# AccelBreakout.net
KiCad netlist of a schematic drawn in EAGLE
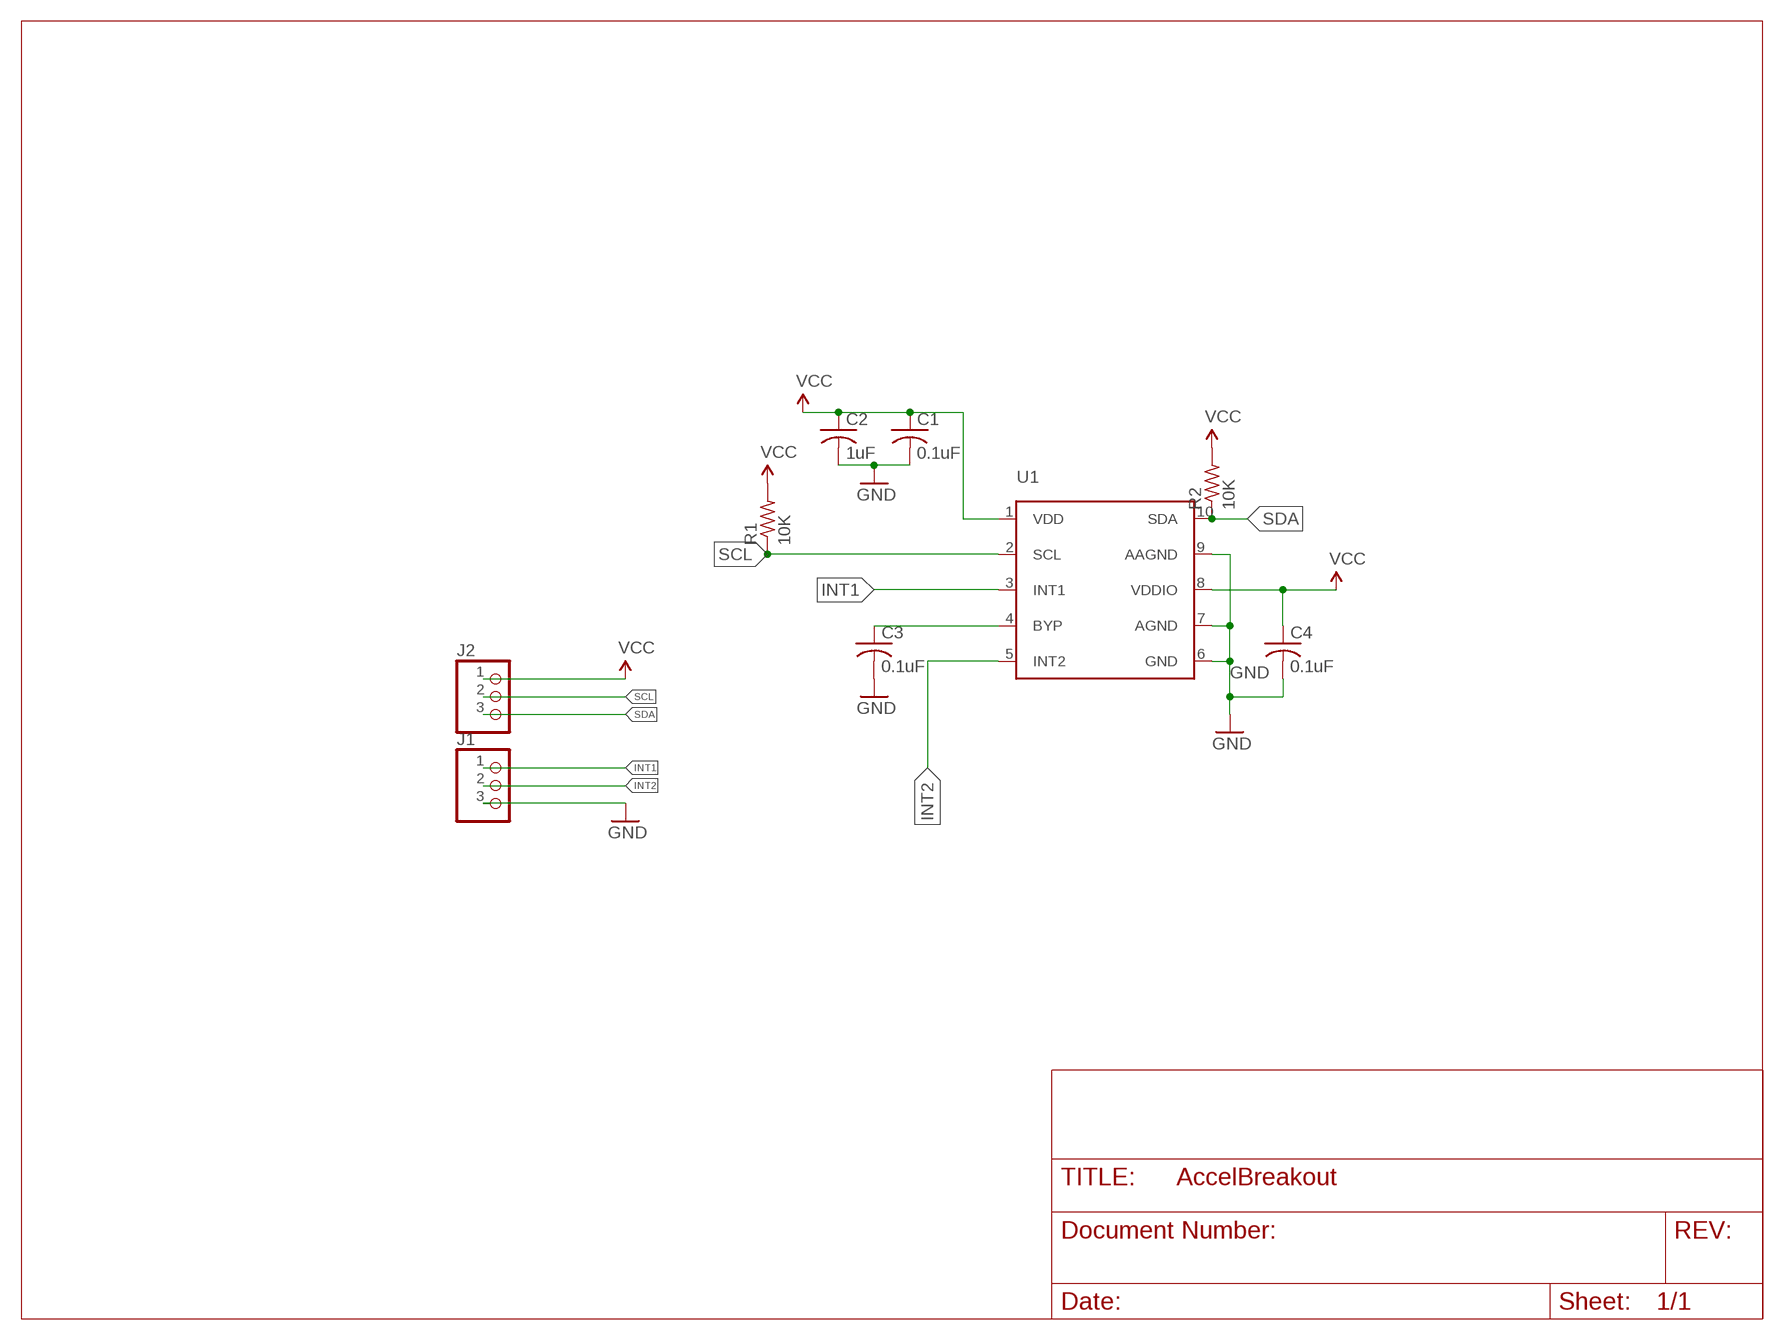
[diagram p0: schematic, sheet 1]

(export (version "E")
  (design (tool "Eeschema 10.0.6"))
  (components
    (comp (ref "C1")
      (value "0.1uF")
      (footprint "eagle-import:C0603")
      (libsource (lib "eagle-import") (part "C-USC0603"))
    )
    (comp (ref "C2")
      (value "1uF")
      (footprint "eagle-import:C0603")
      (libsource (lib "eagle-import") (part "C-USC0603"))
    )
    (comp (ref "C3")
      (value "0.1uF")
      (footprint "eagle-import:C0603")
      (libsource (lib "eagle-import") (part "C-USC0603"))
    )
    (comp (ref "C4")
      (value "0.1uF")
      (footprint "eagle-import:C0603")
      (libsource (lib "eagle-import") (part "C-USC0603"))
    )
    (comp (ref "J1")
      (value "PINHD-1X3")
      (footprint "eagle-import:1X03")
      (libsource (lib "eagle-import") (part "PINHD-1X3"))
    )
    (comp (ref "J2")
      (value "PINHD-1X3")
      (footprint "eagle-import:1X03")
      (libsource (lib "eagle-import") (part "PINHD-1X3"))
    )
    (comp (ref "R1")
      (value "10K")
      (footprint "eagle-import:R0603")
      (libsource (lib "eagle-import") (part "R-US_R0603"))
    )
    (comp (ref "R2")
      (value "10K")
      (footprint "eagle-import:R0603")
      (libsource (lib "eagle-import") (part "R-US_R0603"))
    )
    (comp (ref "U1")
      (value "MMA8653FCR1")
      (footprint "eagle-import:MMA8653FCR1")
      (libsource (lib "eagle-import") (part "MMA8653FCR1"))
    )
  )
  (nets
    (net (code "1") (name "GND") (class "Default")
      (node (ref "C1") (pin "2") (pinfunction "2_2") (pintype "passive"))
      (node (ref "C2") (pin "2") (pinfunction "2_2") (pintype "passive"))
      (node (ref "C3") (pin "2") (pinfunction "2_2") (pintype "passive"))
      (node (ref "C4") (pin "2") (pinfunction "2_2") (pintype "passive"))
      (node (ref "J1") (pin "3") (pinfunction "3_3") (pintype "passive"))
      (node (ref "U1") (pin "6") (pinfunction "GND_6") (pintype "bidirectional"))
      (node (ref "U1") (pin "7") (pinfunction "AGND_7") (pintype "bidirectional"))
      (node (ref "U1") (pin "9") (pinfunction "AAGND_9") (pintype "bidirectional"))
    )
    (net (code "2") (name "INT1") (class "Default")
      (node (ref "J1") (pin "1") (pinfunction "1_1") (pintype "passive"))
      (node (ref "U1") (pin "3") (pinfunction "INT1_3") (pintype "bidirectional"))
    )
    (net (code "3") (name "INT2") (class "Default")
      (node (ref "J1") (pin "2") (pinfunction "2_2") (pintype "passive"))
      (node (ref "U1") (pin "5") (pinfunction "INT2_5") (pintype "bidirectional"))
    )
    (net (code "4") (name "Net-(U1-BYP)") (class "Default")
      (node (ref "C3") (pin "1") (pinfunction "1_1") (pintype "passive"))
      (node (ref "U1") (pin "4") (pinfunction "BYP_4") (pintype "bidirectional"))
    )
    (net (code "5") (name "SCL") (class "Default")
      (node (ref "J2") (pin "2") (pinfunction "2_2") (pintype "passive"))
      (node (ref "R1") (pin "1") (pinfunction "1_1") (pintype "passive"))
      (node (ref "U1") (pin "2") (pinfunction "SCL_2") (pintype "bidirectional"))
    )
    (net (code "6") (name "SDA") (class "Default")
      (node (ref "J2") (pin "3") (pinfunction "3_3") (pintype "passive"))
      (node (ref "R2") (pin "1") (pinfunction "1_1") (pintype "passive"))
      (node (ref "U1") (pin "10") (pinfunction "SDA_10") (pintype "bidirectional"))
    )
    (net (code "7") (name "VCC") (class "Default")
      (node (ref "C1") (pin "1") (pinfunction "1_1") (pintype "passive"))
      (node (ref "C2") (pin "1") (pinfunction "1_1") (pintype "passive"))
      (node (ref "C4") (pin "1") (pinfunction "1_1") (pintype "passive"))
      (node (ref "J2") (pin "1") (pinfunction "1_1") (pintype "passive"))
      (node (ref "R1") (pin "2") (pinfunction "2_2") (pintype "passive"))
      (node (ref "R2") (pin "2") (pinfunction "2_2") (pintype "passive"))
      (node (ref "U1") (pin "1") (pinfunction "VDD_1") (pintype "bidirectional"))
      (node (ref "U1") (pin "8") (pinfunction "VDDIO_8") (pintype "bidirectional"))
    )
  )
)
